# PIC795MotorBoard.net
KiCad netlist of a schematic drawn in EAGLE
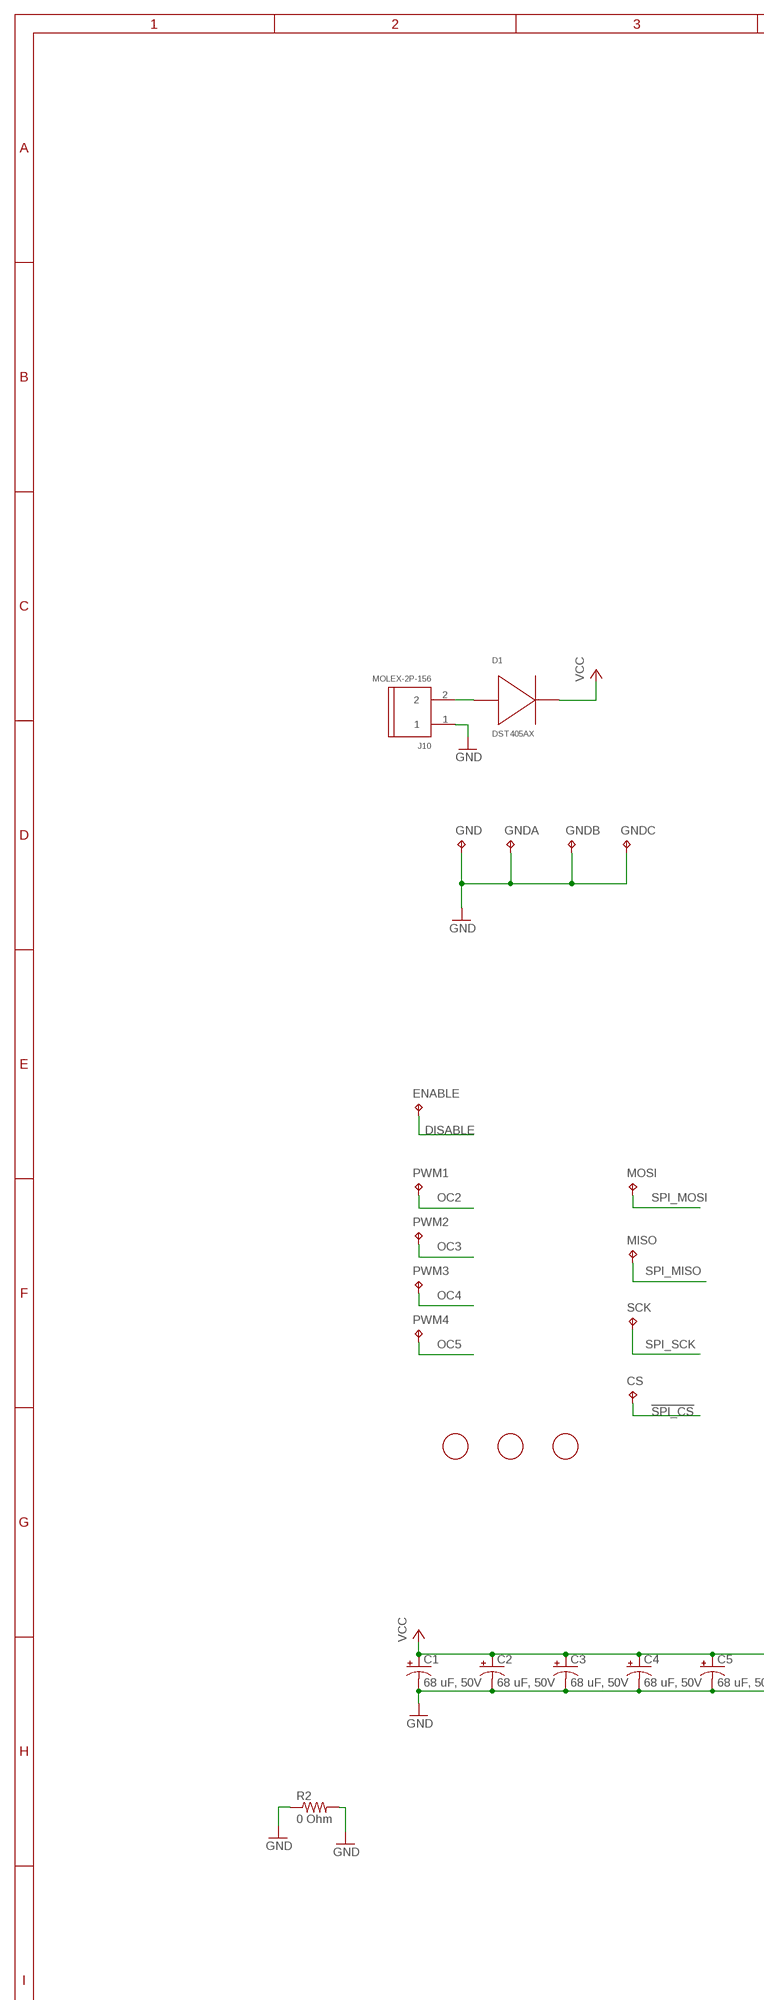
[diagram p0: schematic, sheet 1, part 1 of 2]
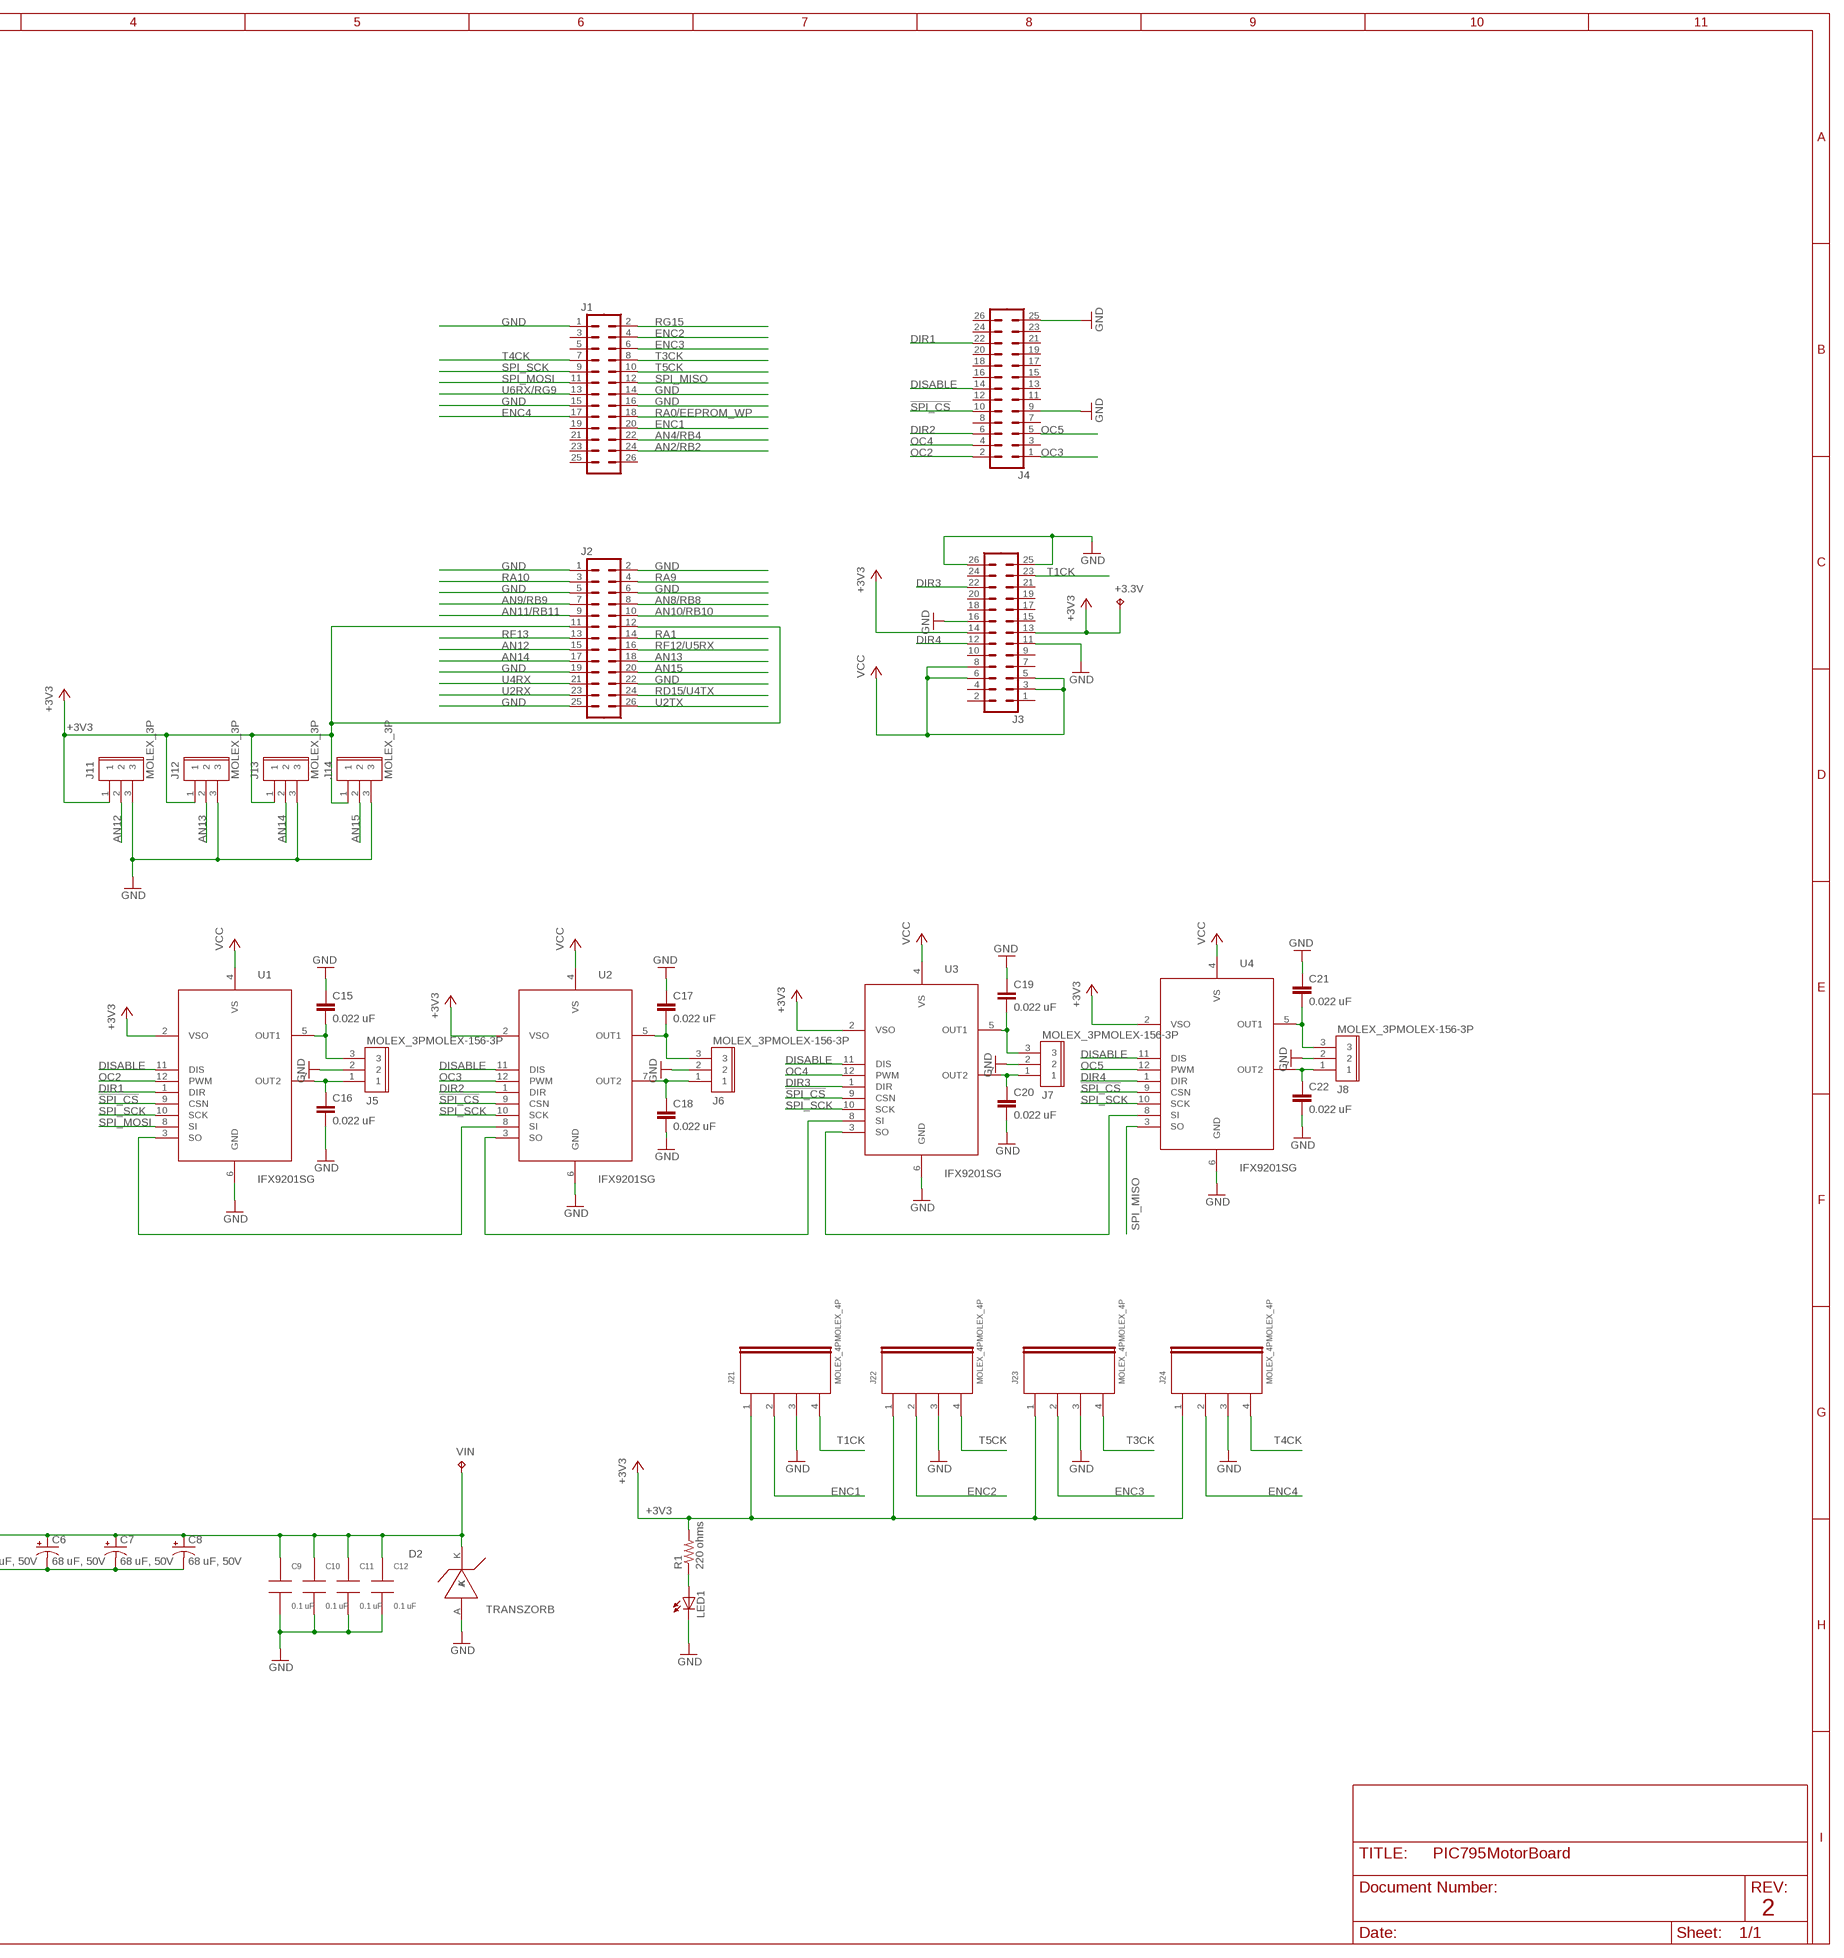
[diagram p1: schematic, sheet 1, part 2 of 2]

(export (version "E")
  (design (tool "Eeschema 10.0.6"))
  (components
    (comp (ref "+3.3V")
      (value "TP")
      (footprint "eagle-import:TESTPAD")
      (libsource (lib "eagle-import") (part "TP"))
    )
    (comp (ref "C1")
      (value "68 uF, 50V")
      (footprint "eagle-import:E3,5-10")
      (libsource (lib "eagle-import") (part "POLCAPE3.5-10"))
    )
    (comp (ref "C2")
      (value "68 uF, 50V")
      (footprint "eagle-import:E3,5-10")
      (libsource (lib "eagle-import") (part "POLCAPE3.5-10"))
    )
    (comp (ref "C3")
      (value "68 uF, 50V")
      (footprint "eagle-import:E3,5-10")
      (libsource (lib "eagle-import") (part "POLCAPE3.5-10"))
    )
    (comp (ref "C4")
      (value "68 uF, 50V")
      (footprint "eagle-import:E3,5-10")
      (libsource (lib "eagle-import") (part "POLCAPE3.5-10"))
    )
    (comp (ref "C5")
      (value "68 uF, 50V")
      (footprint "eagle-import:E3,5-10")
      (libsource (lib "eagle-import") (part "POLCAPE3.5-10"))
    )
    (comp (ref "C6")
      (value "68 uF, 50V")
      (footprint "eagle-import:E3,5-10")
      (libsource (lib "eagle-import") (part "POLCAPE3.5-10"))
    )
    (comp (ref "C7")
      (value "68 uF, 50V")
      (footprint "eagle-import:E3,5-10")
      (libsource (lib "eagle-import") (part "POLCAPE3.5-10"))
    )
    (comp (ref "C8")
      (value "68 uF, 50V")
      (footprint "eagle-import:E3,5-10")
      (libsource (lib "eagle-import") (part "POLCAPE3.5-10"))
    )
    (comp (ref "C9")
      (value "0.1 uF")
      (footprint "eagle-import:C0.3")
      (libsource (lib "eagle-import") (part "CAP-0.300"))
    )
    (comp (ref "C10")
      (value "0.1 uF")
      (footprint "eagle-import:C0.3")
      (libsource (lib "eagle-import") (part "CAP-0.300"))
    )
    (comp (ref "C11")
      (value "0.1 uF")
      (footprint "eagle-import:C0.3")
      (libsource (lib "eagle-import") (part "CAP-0.300"))
    )
    (comp (ref "C12")
      (value "0.1 uF")
      (footprint "eagle-import:C0.3")
      (libsource (lib "eagle-import") (part "CAP-0.300"))
    )
    (comp (ref "C15")
      (value "0.022 uF")
      (footprint "eagle-import:C5B2.5")
      (libsource (lib "eagle-import") (part "C5/2.5"))
    )
    (comp (ref "C16")
      (value "0.022 uF")
      (footprint "eagle-import:C5B2.5")
      (libsource (lib "eagle-import") (part "C5/2.5"))
    )
    (comp (ref "C17")
      (value "0.022 uF")
      (footprint "eagle-import:C5B2.5")
      (libsource (lib "eagle-import") (part "C5/2.5"))
    )
    (comp (ref "C18")
      (value "0.022 uF")
      (footprint "eagle-import:C5B2.5")
      (libsource (lib "eagle-import") (part "C5/2.5"))
    )
    (comp (ref "C19")
      (value "0.022 uF")
      (footprint "eagle-import:C5B2.5")
      (libsource (lib "eagle-import") (part "C5/2.5"))
    )
    (comp (ref "C20")
      (value "0.022 uF")
      (footprint "eagle-import:C5B2.5")
      (libsource (lib "eagle-import") (part "C5/2.5"))
    )
    (comp (ref "C21")
      (value "0.022 uF")
      (footprint "eagle-import:C5B2.5")
      (libsource (lib "eagle-import") (part "C5/2.5"))
    )
    (comp (ref "C22")
      (value "0.022 uF")
      (footprint "eagle-import:C5B2.5")
      (libsource (lib "eagle-import") (part "C5/2.5"))
    )
    (comp (ref "CS")
      (value "TPTESTPAD-SMALL")
      (footprint "eagle-import:TESTPAD-SMALL")
      (libsource (lib "eagle-import") (part "TPTESTPAD-SMALL"))
    )
    (comp (ref "D1")
      (value "DST405AX")
      (footprint "eagle-import:DIODE_10A_THRU")
      (libsource (lib "eagle-import") (part "DIODE_10A_THRU"))
    )
    (comp (ref "D2")
      (value "TRANSZORB")
      (footprint "eagle-import:P600")
      (libsource (lib "eagle-import") (part "TRANSZORB"))
    )
    (comp (ref "ENABLE")
      (value "TPTESTPAD-SMALL")
      (footprint "eagle-import:TESTPAD-SMALL")
      (libsource (lib "eagle-import") (part "TPTESTPAD-SMALL"))
    )
    (comp (ref "GND")
      (value "TP")
      (footprint "eagle-import:TESTPAD")
      (libsource (lib "eagle-import") (part "TP"))
    )
    (comp (ref "GNDA")
      (value "TP")
      (footprint "eagle-import:TESTPAD")
      (libsource (lib "eagle-import") (part "TP"))
    )
    (comp (ref "GNDB")
      (value "TP")
      (footprint "eagle-import:TESTPAD")
      (libsource (lib "eagle-import") (part "TP"))
    )
    (comp (ref "GNDC")
      (value "TP")
      (footprint "eagle-import:TESTPAD")
      (libsource (lib "eagle-import") (part "TP"))
    )
    (comp (ref "J1")
      (value "M13X22X13")
      (footprint "eagle-import:2X13")
      (libsource (lib "eagle-import") (part "M13X22X13"))
    )
    (comp (ref "J2")
      (value "M13X22X13")
      (footprint "eagle-import:2X13")
      (libsource (lib "eagle-import") (part "M13X22X13"))
    )
    (comp (ref "J3")
      (value "M13X22X13")
      (footprint "eagle-import:2X13")
      (libsource (lib "eagle-import") (part "M13X22X13"))
    )
    (comp (ref "J4")
      (value "M13X22X13")
      (footprint "eagle-import:2X13")
      (libsource (lib "eagle-import") (part "M13X22X13"))
    )
    (comp (ref "J5")
      (value "MOLEX_3PMOLEX-156-3P")
      (footprint "eagle-import:MOLEX-156-3")
      (libsource (lib "eagle-import") (part "MOLEX_3PMOLEX-156-3P"))
    )
    (comp (ref "J6")
      (value "MOLEX_3PMOLEX-156-3P")
      (footprint "eagle-import:MOLEX-156-3")
      (libsource (lib "eagle-import") (part "MOLEX_3PMOLEX-156-3P"))
    )
    (comp (ref "J7")
      (value "MOLEX_3PMOLEX-156-3P")
      (footprint "eagle-import:MOLEX-156-3")
      (libsource (lib "eagle-import") (part "MOLEX_3PMOLEX-156-3P"))
    )
    (comp (ref "J8")
      (value "MOLEX_3PMOLEX-156-3P")
      (footprint "eagle-import:MOLEX-156-3")
      (libsource (lib "eagle-import") (part "MOLEX_3PMOLEX-156-3P"))
    )
    (comp (ref "J10")
      (value "MOLEX-2P-156")
      (footprint "eagle-import:MOLEX-156-2P")
      (libsource (lib "eagle-import") (part "MOLEX-2P-156"))
    )
    (comp (ref "J11")
      (value "MOLEX_3P")
      (footprint "eagle-import:MOLEX_3P")
      (libsource (lib "eagle-import") (part "MOLEX_3P"))
    )
    (comp (ref "J12")
      (value "MOLEX_3P")
      (footprint "eagle-import:MOLEX_3P")
      (libsource (lib "eagle-import") (part "MOLEX_3P"))
    )
    (comp (ref "J13")
      (value "MOLEX_3P")
      (footprint "eagle-import:MOLEX_3P")
      (libsource (lib "eagle-import") (part "MOLEX_3P"))
    )
    (comp (ref "J14")
      (value "MOLEX_3P")
      (footprint "eagle-import:MOLEX_3P")
      (libsource (lib "eagle-import") (part "MOLEX_3P"))
    )
    (comp (ref "J21")
      (value "MOLEX_4PMOLEX_4P")
      (footprint "eagle-import:MOLEX_4P")
      (libsource (lib "eagle-import") (part "MOLEX_4PMOLEX_4P"))
    )
    (comp (ref "J22")
      (value "MOLEX_4PMOLEX_4P")
      (footprint "eagle-import:MOLEX_4P")
      (libsource (lib "eagle-import") (part "MOLEX_4PMOLEX_4P"))
    )
    (comp (ref "J23")
      (value "MOLEX_4PMOLEX_4P")
      (footprint "eagle-import:MOLEX_4P")
      (libsource (lib "eagle-import") (part "MOLEX_4PMOLEX_4P"))
    )
    (comp (ref "J24")
      (value "MOLEX_4PMOLEX_4P")
      (footprint "eagle-import:MOLEX_4P")
      (libsource (lib "eagle-import") (part "MOLEX_4PMOLEX_4P"))
    )
    (comp (ref "LED1")
      (value "LED5MM")
      (footprint "eagle-import:LED5MM")
      (libsource (lib "eagle-import") (part "LED5MM"))
    )
    (comp (ref "MISO")
      (value "TPTESTPAD-SMALL")
      (footprint "eagle-import:TESTPAD-SMALL")
      (libsource (lib "eagle-import") (part "TPTESTPAD-SMALL"))
    )
    (comp (ref "MOSI")
      (value "TPTESTPAD-SMALL")
      (footprint "eagle-import:TESTPAD-SMALL")
      (libsource (lib "eagle-import") (part "TPTESTPAD-SMALL"))
    )
    (comp (ref "PWM1")
      (value "TPTESTPAD-SMALL")
      (footprint "eagle-import:TESTPAD-SMALL")
      (libsource (lib "eagle-import") (part "TPTESTPAD-SMALL"))
    )
    (comp (ref "PWM2")
      (value "TPTESTPAD-SMALL")
      (footprint "eagle-import:TESTPAD-SMALL")
      (libsource (lib "eagle-import") (part "TPTESTPAD-SMALL"))
    )
    (comp (ref "PWM3")
      (value "TPTESTPAD-SMALL")
      (footprint "eagle-import:TESTPAD-SMALL")
      (libsource (lib "eagle-import") (part "TPTESTPAD-SMALL"))
    )
    (comp (ref "PWM4")
      (value "TPTESTPAD-SMALL")
      (footprint "eagle-import:TESTPAD-SMALL")
      (libsource (lib "eagle-import") (part "TPTESTPAD-SMALL"))
    )
    (comp (ref "R1")
      (value "220 ohms")
      (footprint "eagle-import:0204_5")
      (libsource (lib "eagle-import") (part "RESISTOR0204/5"))
    )
    (comp (ref "R2")
      (value "0 Ohm")
      (footprint "eagle-import:R0402")
      (libsource (lib "eagle-import") (part "RESISTORR0402"))
    )
    (comp (ref "SCK")
      (value "TPTESTPAD-SMALL")
      (footprint "eagle-import:TESTPAD-SMALL")
      (libsource (lib "eagle-import") (part "TPTESTPAD-SMALL"))
    )
    (comp (ref "U$1")
      (value "FIDUCIAL")
      (footprint "eagle-import:FIDUCIAL_1MM")
      (libsource (lib "eagle-import") (part "FIDUCIAL"))
    )
    (comp (ref "U$2")
      (value "FIDUCIAL")
      (footprint "eagle-import:FIDUCIAL_1MM")
      (libsource (lib "eagle-import") (part "FIDUCIAL"))
    )
    (comp (ref "U$3")
      (value "FIDUCIAL")
      (footprint "eagle-import:FIDUCIAL_1MM")
      (libsource (lib "eagle-import") (part "FIDUCIAL"))
    )
    (comp (ref "U1")
      (value "IFX9201SG")
      (footprint "eagle-import:IFX9201SG")
      (libsource (lib "eagle-import") (part "IFX9201SG"))
    )
    (comp (ref "U2")
      (value "IFX9201SG")
      (footprint "eagle-import:IFX9201SG")
      (libsource (lib "eagle-import") (part "IFX9201SG"))
    )
    (comp (ref "U3")
      (value "IFX9201SG")
      (footprint "eagle-import:IFX9201SG")
      (libsource (lib "eagle-import") (part "IFX9201SG"))
    )
    (comp (ref "U4")
      (value "IFX9201SG")
      (footprint "eagle-import:IFX9201SG")
      (libsource (lib "eagle-import") (part "IFX9201SG"))
    )
    (comp (ref "VIN")
      (value "TP")
      (footprint "eagle-import:TESTPAD")
      (libsource (lib "eagle-import") (part "TP"))
    )
  )
  (nets
    (net (code "1") (name "+3V3") (class "Default")
      (node (ref "+3.3V") (pin "P$1") (pinfunction "TP_P$1") (pintype "input"))
      (node (ref "J11") (pin "1") (pinfunction "1_1") (pintype "bidirectional"))
      (node (ref "J12") (pin "1") (pinfunction "1_1") (pintype "bidirectional"))
      (node (ref "J13") (pin "1") (pinfunction "1_1") (pintype "bidirectional"))
      (node (ref "J14") (pin "1") (pinfunction "1_1") (pintype "bidirectional"))
      (node (ref "J2") (pin "11") (pinfunction "11_11") (pintype "passive"))
      (node (ref "J2") (pin "12") (pinfunction "12_12") (pintype "passive"))
      (node (ref "J21") (pin "1") (pinfunction "1_1") (pintype "bidirectional"))
      (node (ref "J22") (pin "1") (pinfunction "1_1") (pintype "bidirectional"))
      (node (ref "J23") (pin "1") (pinfunction "1_1") (pintype "bidirectional"))
      (node (ref "J24") (pin "1") (pinfunction "1_1") (pintype "bidirectional"))
      (node (ref "J3") (pin "13") (pinfunction "13_13") (pintype "passive"))
      (node (ref "J3") (pin "14") (pinfunction "14_14") (pintype "passive"))
      (node (ref "R1") (pin "2") (pinfunction "2_2") (pintype "passive"))
      (node (ref "U1") (pin "2") (pinfunction "VSO_2") (pintype "bidirectional"))
      (node (ref "U2") (pin "2") (pinfunction "VSO_2") (pintype "bidirectional"))
      (node (ref "U3") (pin "2") (pinfunction "VSO_2") (pintype "bidirectional"))
      (node (ref "U4") (pin "2") (pinfunction "VSO_2") (pintype "bidirectional"))
    )
    (net (code "2") (name "/AN2{slash}RB2") (class "Default")
      (node (ref "J1") (pin "24") (pinfunction "24_24") (pintype "passive"))
    )
    (net (code "3") (name "/AN4{slash}RB4") (class "Default")
      (node (ref "J1") (pin "22") (pinfunction "22_22") (pintype "passive"))
    )
    (net (code "4") (name "/AN8{slash}RB8") (class "Default")
      (node (ref "J2") (pin "8") (pinfunction "8_8") (pintype "passive"))
    )
    (net (code "5") (name "/AN9{slash}RB9") (class "Default")
      (node (ref "J2") (pin "7") (pinfunction "7_7") (pintype "passive"))
    )
    (net (code "6") (name "/AN10{slash}RB10") (class "Default")
      (node (ref "J2") (pin "10") (pinfunction "10_10") (pintype "passive"))
    )
    (net (code "7") (name "/AN11{slash}RB11") (class "Default")
      (node (ref "J2") (pin "9") (pinfunction "9_9") (pintype "passive"))
    )
    (net (code "8") (name "/AN12") (class "Default")
      (node (ref "J11") (pin "2") (pinfunction "2_2") (pintype "bidirectional"))
      (node (ref "J2") (pin "15") (pinfunction "15_15") (pintype "passive"))
    )
    (net (code "9") (name "/AN13") (class "Default")
      (node (ref "J12") (pin "2") (pinfunction "2_2") (pintype "bidirectional"))
      (node (ref "J2") (pin "18") (pinfunction "18_18") (pintype "passive"))
    )
    (net (code "10") (name "/AN14") (class "Default")
      (node (ref "J13") (pin "2") (pinfunction "2_2") (pintype "bidirectional"))
      (node (ref "J2") (pin "17") (pinfunction "17_17") (pintype "passive"))
    )
    (net (code "11") (name "/AN15") (class "Default")
      (node (ref "J14") (pin "2") (pinfunction "2_2") (pintype "bidirectional"))
      (node (ref "J2") (pin "20") (pinfunction "20_20") (pintype "passive"))
    )
    (net (code "12") (name "/DIR1") (class "Default")
      (node (ref "J4") (pin "22") (pinfunction "22_22") (pintype "passive"))
      (node (ref "U1") (pin "1") (pinfunction "DIR_1") (pintype "input"))
    )
    (net (code "13") (name "/DIR2") (class "Default")
      (node (ref "J4") (pin "6") (pinfunction "6_6") (pintype "passive"))
      (node (ref "U2") (pin "1") (pinfunction "DIR_1") (pintype "input"))
    )
    (net (code "14") (name "/DIR3") (class "Default")
      (node (ref "J3") (pin "22") (pinfunction "22_22") (pintype "passive"))
      (node (ref "U3") (pin "1") (pinfunction "DIR_1") (pintype "input"))
    )
    (net (code "15") (name "/DIR4") (class "Default")
      (node (ref "J3") (pin "12") (pinfunction "12_12") (pintype "passive"))
      (node (ref "U4") (pin "1") (pinfunction "DIR_1") (pintype "input"))
    )
    (net (code "16") (name "/DISABLE") (class "Default")
      (node (ref "ENABLE") (pin "P$1") (pinfunction "TP_P$1") (pintype "input"))
      (node (ref "J4") (pin "14") (pinfunction "14_14") (pintype "passive"))
      (node (ref "U1") (pin "11") (pinfunction "DIS_11") (pintype "input"))
      (node (ref "U2") (pin "11") (pinfunction "DIS_11") (pintype "input"))
      (node (ref "U3") (pin "11") (pinfunction "DIS_11") (pintype "input"))
      (node (ref "U4") (pin "11") (pinfunction "DIS_11") (pintype "input"))
    )
    (net (code "17") (name "/ENC1") (class "Default")
      (node (ref "J1") (pin "20") (pinfunction "20_20") (pintype "passive"))
      (node (ref "J21") (pin "2") (pinfunction "2_2") (pintype "bidirectional"))
    )
    (net (code "18") (name "/ENC2") (class "Default")
      (node (ref "J1") (pin "4") (pinfunction "4_4") (pintype "passive"))
      (node (ref "J22") (pin "2") (pinfunction "2_2") (pintype "bidirectional"))
    )
    (net (code "19") (name "/ENC3") (class "Default")
      (node (ref "J1") (pin "6") (pinfunction "6_6") (pintype "passive"))
      (node (ref "J23") (pin "2") (pinfunction "2_2") (pintype "bidirectional"))
    )
    (net (code "20") (name "/ENC4") (class "Default")
      (node (ref "J1") (pin "17") (pinfunction "17_17") (pintype "passive"))
      (node (ref "J24") (pin "2") (pinfunction "2_2") (pintype "bidirectional"))
    )
    (net (code "21") (name "/OC2") (class "Default")
      (node (ref "J4") (pin "2") (pinfunction "2_2") (pintype "passive"))
      (node (ref "PWM1") (pin "P$1") (pinfunction "TP_P$1") (pintype "input"))
      (node (ref "U1") (pin "12") (pinfunction "PWM_12") (pintype "input"))
    )
    (net (code "22") (name "/OC3") (class "Default")
      (node (ref "J4") (pin "1") (pinfunction "1_1") (pintype "passive"))
      (node (ref "PWM2") (pin "P$1") (pinfunction "TP_P$1") (pintype "input"))
      (node (ref "U2") (pin "12") (pinfunction "PWM_12") (pintype "input"))
    )
    (net (code "23") (name "/OC4") (class "Default")
      (node (ref "J4") (pin "4") (pinfunction "4_4") (pintype "passive"))
      (node (ref "PWM3") (pin "P$1") (pinfunction "TP_P$1") (pintype "input"))
      (node (ref "U3") (pin "12") (pinfunction "PWM_12") (pintype "input"))
    )
    (net (code "24") (name "/OC5") (class "Default")
      (node (ref "J4") (pin "5") (pinfunction "5_5") (pintype "passive"))
      (node (ref "PWM4") (pin "P$1") (pinfunction "TP_P$1") (pintype "input"))
      (node (ref "U4") (pin "12") (pinfunction "PWM_12") (pintype "input"))
    )
    (net (code "25") (name "/RA0{slash}EEPROM_WP") (class "Default")
      (node (ref "J1") (pin "18") (pinfunction "18_18") (pintype "passive"))
    )
    (net (code "26") (name "/RA1") (class "Default")
      (node (ref "J2") (pin "14") (pinfunction "14_14") (pintype "passive"))
    )
    (net (code "27") (name "/RA9") (class "Default")
      (node (ref "J2") (pin "4") (pinfunction "4_4") (pintype "passive"))
    )
    (net (code "28") (name "/RA10") (class "Default")
      (node (ref "J2") (pin "3") (pinfunction "3_3") (pintype "passive"))
    )
    (net (code "29") (name "/RD15{slash}U4TX") (class "Default")
      (node (ref "J2") (pin "24") (pinfunction "24_24") (pintype "passive"))
    )
    (net (code "30") (name "/RF12{slash}U5RX") (class "Default")
      (node (ref "J2") (pin "16") (pinfunction "16_16") (pintype "passive"))
    )
    (net (code "31") (name "/RF13") (class "Default")
      (node (ref "J2") (pin "13") (pinfunction "13_13") (pintype "passive"))
    )
    (net (code "32") (name "/RG15") (class "Default")
      (node (ref "J1") (pin "2") (pinfunction "2_2") (pintype "passive"))
    )
    (net (code "33") (name "/SPI_MISO") (class "Default")
      (node (ref "J1") (pin "12") (pinfunction "12_12") (pintype "passive"))
      (node (ref "MISO") (pin "P$1") (pinfunction "TP_P$1") (pintype "input"))
      (node (ref "U4") (pin "3") (pinfunction "SO_3") (pintype "output"))
    )
    (net (code "34") (name "/SPI_MOSI") (class "Default")
      (node (ref "J1") (pin "11") (pinfunction "11_11") (pintype "passive"))
      (node (ref "MOSI") (pin "P$1") (pinfunction "TP_P$1") (pintype "input"))
      (node (ref "U1") (pin "8") (pinfunction "SI_8") (pintype "input"))
    )
    (net (code "35") (name "/SPI_SCK") (class "Default")
      (node (ref "J1") (pin "9") (pinfunction "9_9") (pintype "passive"))
      (node (ref "SCK") (pin "P$1") (pinfunction "TP_P$1") (pintype "input"))
      (node (ref "U1") (pin "10") (pinfunction "SCK_10") (pintype "input"))
      (node (ref "U2") (pin "10") (pinfunction "SCK_10") (pintype "input"))
      (node (ref "U3") (pin "10") (pinfunction "SCK_10") (pintype "input"))
      (node (ref "U4") (pin "10") (pinfunction "SCK_10") (pintype "input"))
    )
    (net (code "36") (name "/T1CK") (class "Default")
      (node (ref "J21") (pin "4") (pinfunction "4_4") (pintype "bidirectional"))
      (node (ref "J3") (pin "23") (pinfunction "23_23") (pintype "passive"))
    )
    (net (code "37") (name "/T3CK") (class "Default")
      (node (ref "J1") (pin "8") (pinfunction "8_8") (pintype "passive"))
      (node (ref "J23") (pin "4") (pinfunction "4_4") (pintype "bidirectional"))
    )
    (net (code "38") (name "/T4CK") (class "Default")
      (node (ref "J1") (pin "7") (pinfunction "7_7") (pintype "passive"))
      (node (ref "J24") (pin "4") (pinfunction "4_4") (pintype "bidirectional"))
    )
    (net (code "39") (name "/T5CK") (class "Default")
      (node (ref "J1") (pin "10") (pinfunction "10_10") (pintype "passive"))
      (node (ref "J22") (pin "4") (pinfunction "4_4") (pintype "bidirectional"))
    )
    (net (code "40") (name "/U2RX") (class "Default")
      (node (ref "J2") (pin "23") (pinfunction "23_23") (pintype "passive"))
    )
    (net (code "41") (name "/U2TX") (class "Default")
      (node (ref "J2") (pin "26") (pinfunction "26_26") (pintype "passive"))
    )
    (net (code "42") (name "/U4RX") (class "Default")
      (node (ref "J2") (pin "21") (pinfunction "21_21") (pintype "passive"))
    )
    (net (code "43") (name "/U6RX{slash}RG9") (class "Default")
      (node (ref "J1") (pin "13") (pinfunction "13_13") (pintype "passive"))
    )
    (net (code "44") (name "/~{SPI_CS}") (class "Default")
      (node (ref "CS") (pin "P$1") (pinfunction "TP_P$1") (pintype "input"))
      (node (ref "J4") (pin "10") (pinfunction "10_10") (pintype "passive"))
      (node (ref "U1") (pin "9") (pinfunction "CSN_9") (pintype "input"))
      (node (ref "U2") (pin "9") (pinfunction "CSN_9") (pintype "input"))
      (node (ref "U3") (pin "9") (pinfunction "CSN_9") (pintype "input"))
      (node (ref "U4") (pin "9") (pinfunction "CSN_9") (pintype "input"))
    )
    (net (code "45") (name "GND") (class "Default")
      (node (ref "C1") (pin "-") (pinfunction "-_-") (pintype "passive"))
      (node (ref "C10") (pin "2") (pinfunction "1_2") (pintype "bidirectional"))
      (node (ref "C11") (pin "2") (pinfunction "1_2") (pintype "bidirectional"))
      (node (ref "C12") (pin "2") (pinfunction "1_2") (pintype "bidirectional"))
      (node (ref "C15") (pin "1") (pinfunction "1_1") (pintype "passive"))
      (node (ref "C16") (pin "2") (pinfunction "2_2") (pintype "passive"))
      (node (ref "C17") (pin "1") (pinfunction "1_1") (pintype "passive"))
      (node (ref "C18") (pin "2") (pinfunction "2_2") (pintype "passive"))
      (node (ref "C19") (pin "1") (pinfunction "1_1") (pintype "passive"))
      (node (ref "C2") (pin "-") (pinfunction "-_-") (pintype "passive"))
      (node (ref "C20") (pin "2") (pinfunction "2_2") (pintype "passive"))
      (node (ref "C21") (pin "1") (pinfunction "1_1") (pintype "passive"))
      (node (ref "C22") (pin "2") (pinfunction "2_2") (pintype "passive"))
      (node (ref "C3") (pin "-") (pinfunction "-_-") (pintype "passive"))
      (node (ref "C4") (pin "-") (pinfunction "-_-") (pintype "passive"))
      (node (ref "C5") (pin "-") (pinfunction "-_-") (pintype "passive"))
      (node (ref "C6") (pin "-") (pinfunction "-_-") (pintype "passive"))
      (node (ref "C7") (pin "-") (pinfunction "-_-") (pintype "passive"))
      (node (ref "C8") (pin "-") (pinfunction "-_-") (pintype "passive"))
      (node (ref "C9") (pin "2") (pinfunction "1_2") (pintype "bidirectional"))
      (node (ref "D2") (pin "A") (pinfunction "A_A") (pintype "bidirectional"))
      (node (ref "GND") (pin "P$1") (pinfunction "TP_P$1") (pintype "input"))
      (node (ref "GNDA") (pin "P$1") (pinfunction "TP_P$1") (pintype "input"))
      (node (ref "GNDB") (pin "P$1") (pinfunction "TP_P$1") (pintype "input"))
      (node (ref "GNDC") (pin "P$1") (pinfunction "TP_P$1") (pintype "input"))
      (node (ref "J1") (pin "1") (pinfunction "1_1") (pintype "passive"))
      (node (ref "J1") (pin "14") (pinfunction "14_14") (pintype "passive"))
      (node (ref "J1") (pin "15") (pinfunction "15_15") (pintype "passive"))
      (node (ref "J1") (pin "16") (pinfunction "16_16") (pintype "passive"))
      (node (ref "J10") (pin "1") (pinfunction "1_1") (pintype "bidirectional"))
      (node (ref "J11") (pin "3") (pinfunction "3_3") (pintype "bidirectional"))
      (node (ref "J12") (pin "3") (pinfunction "3_3") (pintype "bidirectional"))
      (node (ref "J13") (pin "3") (pinfunction "3_3") (pintype "bidirectional"))
      (node (ref "J14") (pin "3") (pinfunction "3_3") (pintype "bidirectional"))
      (node (ref "J2") (pin "1") (pinfunction "1_1") (pintype "passive"))
      (node (ref "J2") (pin "19") (pinfunction "19_19") (pintype "passive"))
      (node (ref "J2") (pin "2") (pinfunction "2_2") (pintype "passive"))
      (node (ref "J2") (pin "22") (pinfunction "22_22") (pintype "passive"))
      (node (ref "J2") (pin "25") (pinfunction "25_25") (pintype "passive"))
      (node (ref "J2") (pin "5") (pinfunction "5_5") (pintype "passive"))
      (node (ref "J2") (pin "6") (pinfunction "6_6") (pintype "passive"))
      (node (ref "J21") (pin "3") (pinfunction "3_3") (pintype "bidirectional"))
      (node (ref "J22") (pin "3") (pinfunction "3_3") (pintype "bidirectional"))
      (node (ref "J23") (pin "3") (pinfunction "3_3") (pintype "bidirectional"))
      (node (ref "J24") (pin "3") (pinfunction "3_3") (pintype "bidirectional"))
      (node (ref "J3") (pin "11") (pinfunction "11_11") (pintype "passive"))
      (node (ref "J3") (pin "16") (pinfunction "16_16") (pintype "passive"))
      (node (ref "J3") (pin "25") (pinfunction "25_25") (pintype "passive"))
      (node (ref "J3") (pin "26") (pinfunction "26_26") (pintype "passive"))
      (node (ref "J4") (pin "25") (pinfunction "25_25") (pintype "passive"))
      (node (ref "J4") (pin "9") (pinfunction "9_9") (pintype "passive"))
      (node (ref "J5") (pin "2") (pinfunction "2_2") (pintype "bidirectional"))
      (node (ref "J6") (pin "2") (pinfunction "2_2") (pintype "bidirectional"))
      (node (ref "J7") (pin "2") (pinfunction "2_2") (pintype "bidirectional"))
      (node (ref "J8") (pin "2") (pinfunction "2_2") (pintype "bidirectional"))
      (node (ref "LED1") (pin "K") (pinfunction "C_K") (pintype "passive"))
      (node (ref "R2") (pin "1") (pinfunction "1_1") (pintype "passive"))
      (node (ref "R2") (pin "2") (pinfunction "2_2") (pintype "passive"))
      (node (ref "U1") (pin "6") (pinfunction "GND_6") (pintype "power_in"))
      (node (ref "U2") (pin "6") (pinfunction "GND_6") (pintype "power_in"))
      (node (ref "U3") (pin "6") (pinfunction "GND_6") (pintype "power_in"))
      (node (ref "U4") (pin "6") (pinfunction "GND_6") (pintype "power_in"))
    )
    (net (code "46") (name "Net-(D1-ANODE)") (class "Default")
      (node (ref "D1") (pin "P$1") (pinfunction "ANODE_P$1") (pintype "bidirectional"))
      (node (ref "J10") (pin "2") (pinfunction "2_2") (pintype "bidirectional"))
    )
    (net (code "47") (name "Net-(LED1-PadA)") (class "Default")
      (node (ref "LED1") (pin "A") (pinfunction "A_A") (pintype "passive"))
      (node (ref "R1") (pin "1") (pinfunction "1_1") (pintype "passive"))
    )
    (net (code "48") (name "Net-(U1-OUT1)") (class "Default")
      (node (ref "C15") (pin "2") (pinfunction "2_2") (pintype "passive"))
      (node (ref "J5") (pin "3") (pinfunction "3_3") (pintype "bidirectional"))
      (node (ref "U1") (pin "5") (pinfunction "OUT1_5") (pintype "output"))
    )
    (net (code "49") (name "Net-(U1-OUT2)") (class "Default")
      (node (ref "C16") (pin "1") (pinfunction "1_1") (pintype "passive"))
      (node (ref "J5") (pin "1") (pinfunction "1_1") (pintype "bidirectional"))
      (node (ref "U1") (pin "7") (pinfunction "OUT2_7") (pintype "output"))
    )
    (net (code "50") (name "Net-(U1-SO)") (class "Default")
      (node (ref "U1") (pin "3") (pinfunction "SO_3") (pintype "output"))
      (node (ref "U2") (pin "8") (pinfunction "SI_8") (pintype "input"))
    )
    (net (code "51") (name "Net-(U2-OUT1)") (class "Default")
      (node (ref "C17") (pin "2") (pinfunction "2_2") (pintype "passive"))
      (node (ref "J6") (pin "3") (pinfunction "3_3") (pintype "bidirectional"))
      (node (ref "U2") (pin "5") (pinfunction "OUT1_5") (pintype "output"))
    )
    (net (code "52") (name "Net-(U2-OUT2)") (class "Default")
      (node (ref "C18") (pin "1") (pinfunction "1_1") (pintype "passive"))
      (node (ref "J6") (pin "1") (pinfunction "1_1") (pintype "bidirectional"))
      (node (ref "U2") (pin "7") (pinfunction "OUT2_7") (pintype "output"))
    )
    (net (code "53") (name "Net-(U2-SO)") (class "Default")
      (node (ref "U2") (pin "3") (pinfunction "SO_3") (pintype "output"))
      (node (ref "U3") (pin "8") (pinfunction "SI_8") (pintype "input"))
    )
    (net (code "54") (name "Net-(U3-OUT1)") (class "Default")
      (node (ref "C19") (pin "2") (pinfunction "2_2") (pintype "passive"))
      (node (ref "J7") (pin "3") (pinfunction "3_3") (pintype "bidirectional"))
      (node (ref "U3") (pin "5") (pinfunction "OUT1_5") (pintype "output"))
    )
    (net (code "55") (name "Net-(U3-OUT2)") (class "Default")
      (node (ref "C20") (pin "1") (pinfunction "1_1") (pintype "passive"))
      (node (ref "J7") (pin "1") (pinfunction "1_1") (pintype "bidirectional"))
      (node (ref "U3") (pin "7") (pinfunction "OUT2_7") (pintype "output"))
    )
    (net (code "56") (name "Net-(U3-SO)") (class "Default")
      (node (ref "U3") (pin "3") (pinfunction "SO_3") (pintype "output"))
      (node (ref "U4") (pin "8") (pinfunction "SI_8") (pintype "input"))
    )
    (net (code "57") (name "Net-(U4-OUT1)") (class "Default")
      (node (ref "C21") (pin "2") (pinfunction "2_2") (pintype "passive"))
      (node (ref "J8") (pin "3") (pinfunction "3_3") (pintype "bidirectional"))
      (node (ref "U4") (pin "5") (pinfunction "OUT1_5") (pintype "output"))
    )
    (net (code "58") (name "Net-(U4-OUT2)") (class "Default")
      (node (ref "C22") (pin "1") (pinfunction "1_1") (pintype "passive"))
      (node (ref "J8") (pin "1") (pinfunction "1_1") (pintype "bidirectional"))
      (node (ref "U4") (pin "7") (pinfunction "OUT2_7") (pintype "output"))
    )
    (net (code "59") (name "VCC") (class "Default")
      (node (ref "C1") (pin "+") (pinfunction "+_+") (pintype "passive"))
      (node (ref "C10") (pin "1") (pinfunction "2_1") (pintype "bidirectional"))
      (node (ref "C11") (pin "1") (pinfunction "2_1") (pintype "bidirectional"))
      (node (ref "C12") (pin "1") (pinfunction "2_1") (pintype "bidirectional"))
      (node (ref "C2") (pin "+") (pinfunction "+_+") (pintype "passive"))
      (node (ref "C3") (pin "+") (pinfunction "+_+") (pintype "passive"))
      (node (ref "C4") (pin "+") (pinfunction "+_+") (pintype "passive"))
      (node (ref "C5") (pin "+") (pinfunction "+_+") (pintype "passive"))
      (node (ref "C6") (pin "+") (pinfunction "+_+") (pintype "passive"))
      (node (ref "C7") (pin "+") (pinfunction "+_+") (pintype "passive"))
      (node (ref "C8") (pin "+") (pinfunction "+_+") (pintype "passive"))
      (node (ref "C9") (pin "1") (pinfunction "2_1") (pintype "bidirectional"))
      (node (ref "D1") (pin "P$2") (pinfunction "CATHODE_P$2") (pintype "bidirectional"))
      (node (ref "D2") (pin "K") (pinfunction "K_K") (pintype "bidirectional"))
      (node (ref "J3") (pin "3") (pinfunction "3_3") (pintype "passive"))
      (node (ref "J3") (pin "5") (pinfunction "5_5") (pintype "passive"))
      (node (ref "J3") (pin "6") (pinfunction "6_6") (pintype "passive"))
      (node (ref "J3") (pin "8") (pinfunction "8_8") (pintype "passive"))
      (node (ref "U1") (pin "4") (pinfunction "VS_4") (pintype "power_in"))
      (node (ref "U2") (pin "4") (pinfunction "VS_4") (pintype "power_in"))
      (node (ref "U3") (pin "4") (pinfunction "VS_4") (pintype "power_in"))
      (node (ref "U4") (pin "4") (pinfunction "VS_4") (pintype "power_in"))
      (node (ref "VIN") (pin "P$1") (pinfunction "TP_P$1") (pintype "input"))
    )
    (net (code "60") (name "unconnected-(J1-Pad3)") (class "Default")
      (node (ref "J1") (pin "3") (pinfunction "3_3") (pintype "passive"))
    )
    (net (code "61") (name "unconnected-(J1-Pad5)") (class "Default")
      (node (ref "J1") (pin "5") (pinfunction "5_5") (pintype "passive"))
    )
    (net (code "62") (name "unconnected-(J1-Pad19)") (class "Default")
      (node (ref "J1") (pin "19") (pinfunction "19_19") (pintype "passive"))
    )
    (net (code "63") (name "unconnected-(J1-Pad21)") (class "Default")
      (node (ref "J1") (pin "21") (pinfunction "21_21") (pintype "passive"))
    )
    (net (code "64") (name "unconnected-(J1-Pad23)") (class "Default")
      (node (ref "J1") (pin "23") (pinfunction "23_23") (pintype "passive"))
    )
    (net (code "65") (name "unconnected-(J1-Pad25)") (class "Default")
      (node (ref "J1") (pin "25") (pinfunction "25_25") (pintype "passive"))
    )
    (net (code "66") (name "unconnected-(J1-Pad26)") (class "Default")
      (node (ref "J1") (pin "26") (pinfunction "26_26") (pintype "passive"))
    )
    (net (code "67") (name "unconnected-(J3-Pad1)") (class "Default")
      (node (ref "J3") (pin "1") (pinfunction "1_1") (pintype "passive"))
    )
    (net (code "68") (name "unconnected-(J3-Pad2)") (class "Default")
      (node (ref "J3") (pin "2") (pinfunction "2_2") (pintype "passive"))
    )
    (net (code "69") (name "unconnected-(J3-Pad4)") (class "Default")
      (node (ref "J3") (pin "4") (pinfunction "4_4") (pintype "passive"))
    )
    (net (code "70") (name "unconnected-(J3-Pad7)") (class "Default")
      (node (ref "J3") (pin "7") (pinfunction "7_7") (pintype "passive"))
    )
    (net (code "71") (name "unconnected-(J3-Pad9)") (class "Default")
      (node (ref "J3") (pin "9") (pinfunction "9_9") (pintype "passive"))
    )
    (net (code "72") (name "unconnected-(J3-Pad10)") (class "Default")
      (node (ref "J3") (pin "10") (pinfunction "10_10") (pintype "passive"))
    )
    (net (code "73") (name "unconnected-(J3-Pad15)") (class "Default")
      (node (ref "J3") (pin "15") (pinfunction "15_15") (pintype "passive"))
    )
    (net (code "74") (name "unconnected-(J3-Pad17)") (class "Default")
      (node (ref "J3") (pin "17") (pinfunction "17_17") (pintype "passive"))
    )
    (net (code "75") (name "unconnected-(J3-Pad18)") (class "Default")
      (node (ref "J3") (pin "18") (pinfunction "18_18") (pintype "passive"))
    )
    (net (code "76") (name "unconnected-(J3-Pad19)") (class "Default")
      (node (ref "J3") (pin "19") (pinfunction "19_19") (pintype "passive"))
    )
    (net (code "77") (name "unconnected-(J3-Pad20)") (class "Default")
      (node (ref "J3") (pin "20") (pinfunction "20_20") (pintype "passive"))
    )
    (net (code "78") (name "unconnected-(J3-Pad21)") (class "Default")
      (node (ref "J3") (pin "21") (pinfunction "21_21") (pintype "passive"))
    )
    (net (code "79") (name "unconnected-(J3-Pad24)") (class "Default")
      (node (ref "J3") (pin "24") (pinfunction "24_24") (pintype "passive"))
    )
    (net (code "80") (name "unconnected-(J4-Pad3)") (class "Default")
      (node (ref "J4") (pin "3") (pinfunction "3_3") (pintype "passive"))
    )
    (net (code "81") (name "unconnected-(J4-Pad7)") (class "Default")
      (node (ref "J4") (pin "7") (pinfunction "7_7") (pintype "passive"))
    )
    (net (code "82") (name "unconnected-(J4-Pad8)") (class "Default")
      (node (ref "J4") (pin "8") (pinfunction "8_8") (pintype "passive"))
    )
    (net (code "83") (name "unconnected-(J4-Pad11)") (class "Default")
      (node (ref "J4") (pin "11") (pinfunction "11_11") (pintype "passive"))
    )
    (net (code "84") (name "unconnected-(J4-Pad12)") (class "Default")
      (node (ref "J4") (pin "12") (pinfunction "12_12") (pintype "passive"))
    )
    (net (code "85") (name "unconnected-(J4-Pad13)") (class "Default")
      (node (ref "J4") (pin "13") (pinfunction "13_13") (pintype "passive"))
    )
    (net (code "86") (name "unconnected-(J4-Pad15)") (class "Default")
      (node (ref "J4") (pin "15") (pinfunction "15_15") (pintype "passive"))
    )
    (net (code "87") (name "unconnected-(J4-Pad16)") (class "Default")
      (node (ref "J4") (pin "16") (pinfunction "16_16") (pintype "passive"))
    )
    (net (code "88") (name "unconnected-(J4-Pad17)") (class "Default")
      (node (ref "J4") (pin "17") (pinfunction "17_17") (pintype "passive"))
    )
    (net (code "89") (name "unconnected-(J4-Pad18)") (class "Default")
      (node (ref "J4") (pin "18") (pinfunction "18_18") (pintype "passive"))
    )
    (net (code "90") (name "unconnected-(J4-Pad19)") (class "Default")
      (node (ref "J4") (pin "19") (pinfunction "19_19") (pintype "passive"))
    )
    (net (code "91") (name "unconnected-(J4-Pad20)") (class "Default")
      (node (ref "J4") (pin "20") (pinfunction "20_20") (pintype "passive"))
    )
    (net (code "92") (name "unconnected-(J4-Pad21)") (class "Default")
      (node (ref "J4") (pin "21") (pinfunction "21_21") (pintype "passive"))
    )
    (net (code "93") (name "unconnected-(J4-Pad23)") (class "Default")
      (node (ref "J4") (pin "23") (pinfunction "23_23") (pintype "passive"))
    )
    (net (code "94") (name "unconnected-(J4-Pad24)") (class "Default")
      (node (ref "J4") (pin "24") (pinfunction "24_24") (pintype "passive"))
    )
    (net (code "95") (name "unconnected-(J4-Pad26)") (class "Default")
      (node (ref "J4") (pin "26") (pinfunction "26_26") (pintype "passive"))
    )
  )
)
